# VM3300_V0_1.net
KiCad netlist of a schematic drawn in Altium Designer
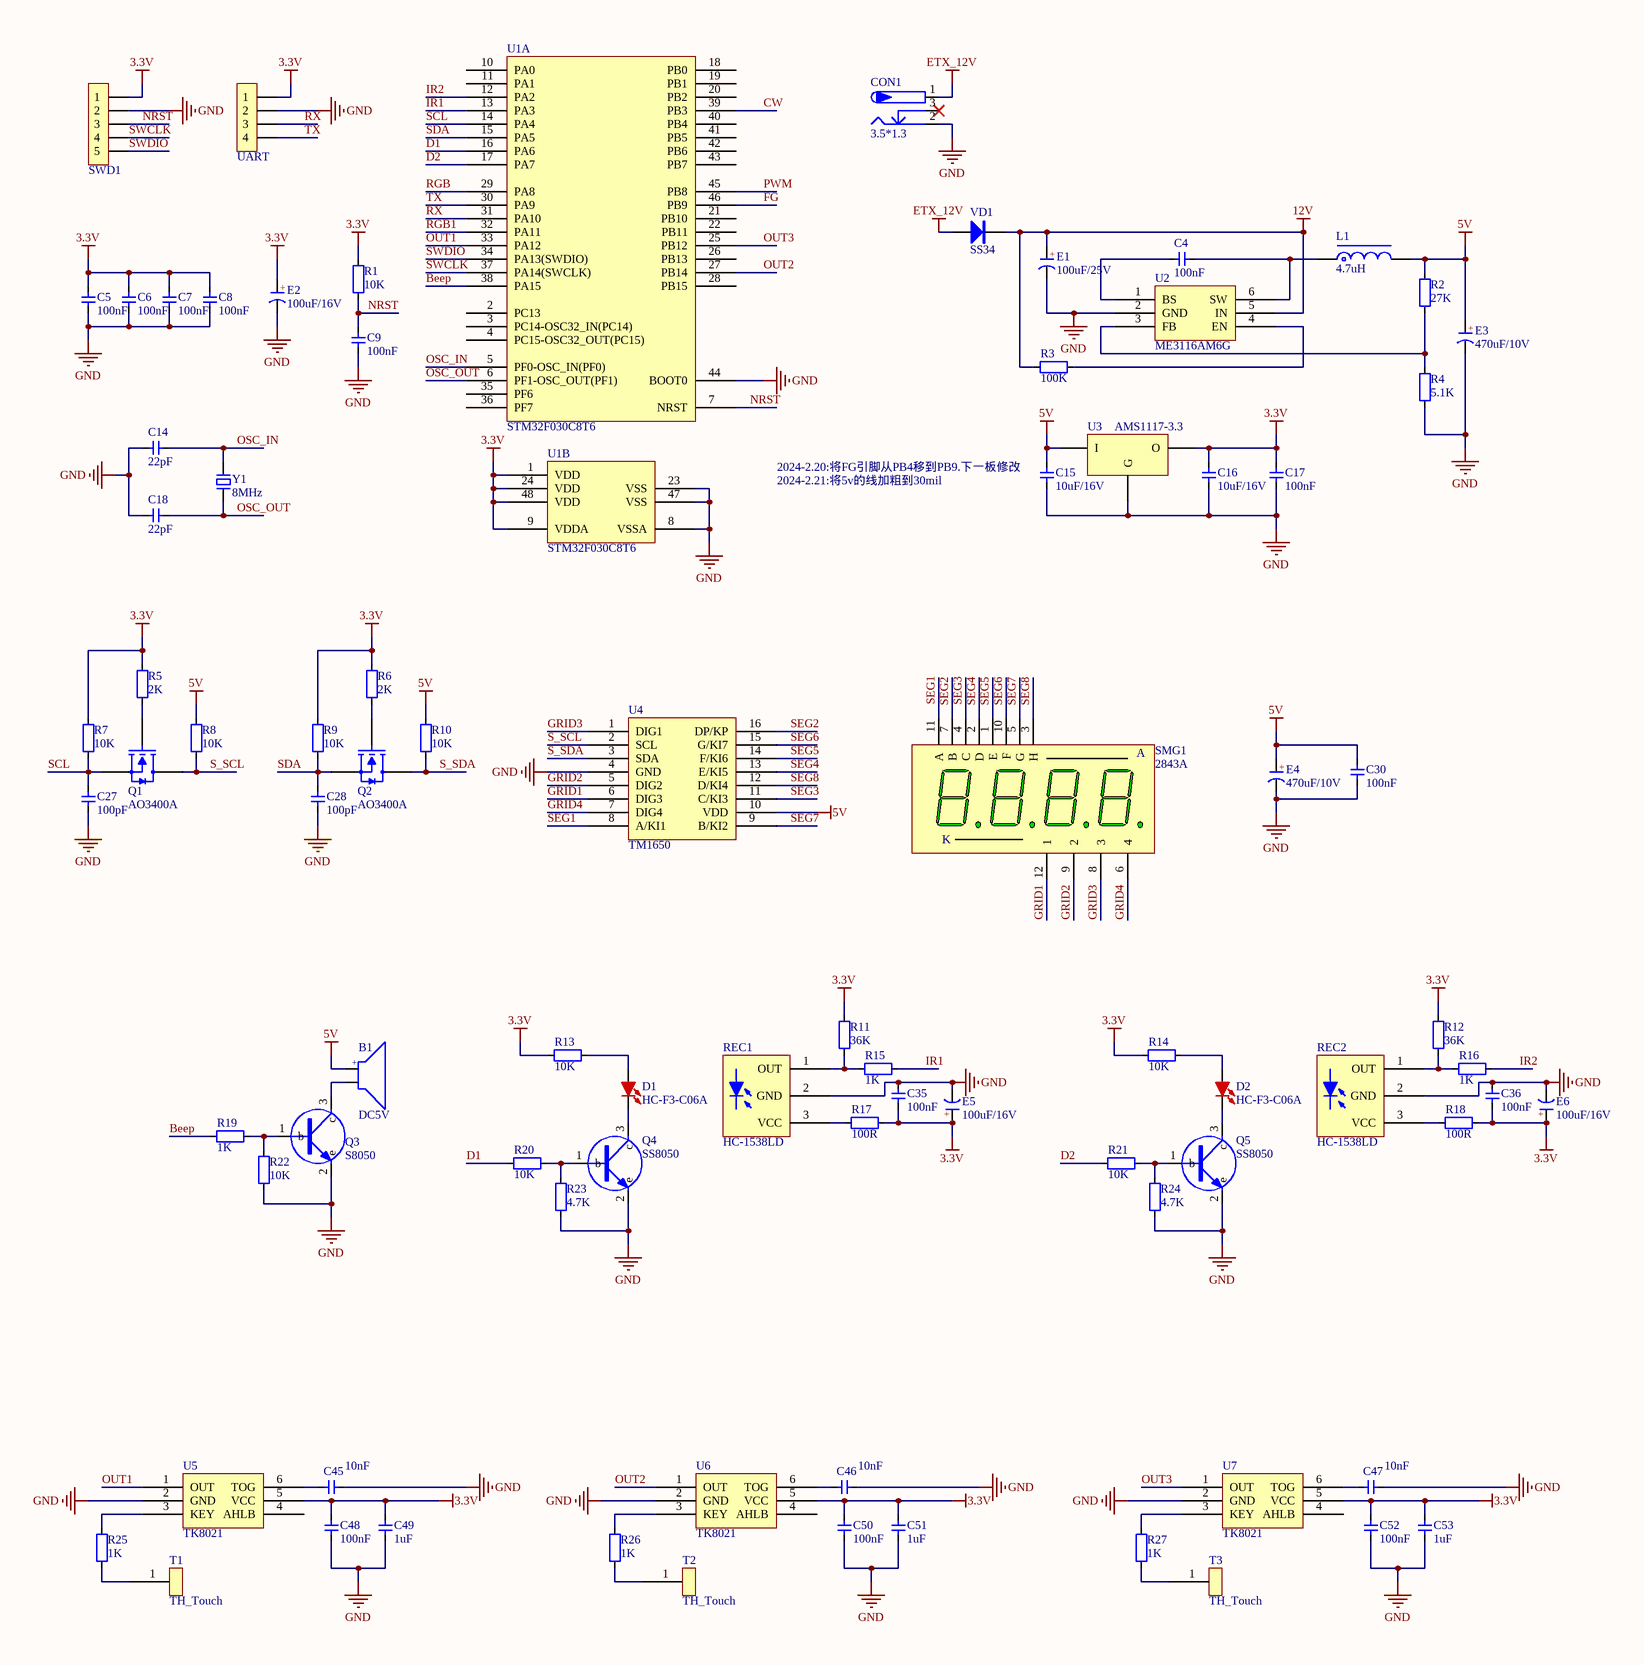
[diagram p0: VM3300_V0.1.SchDoc, left]
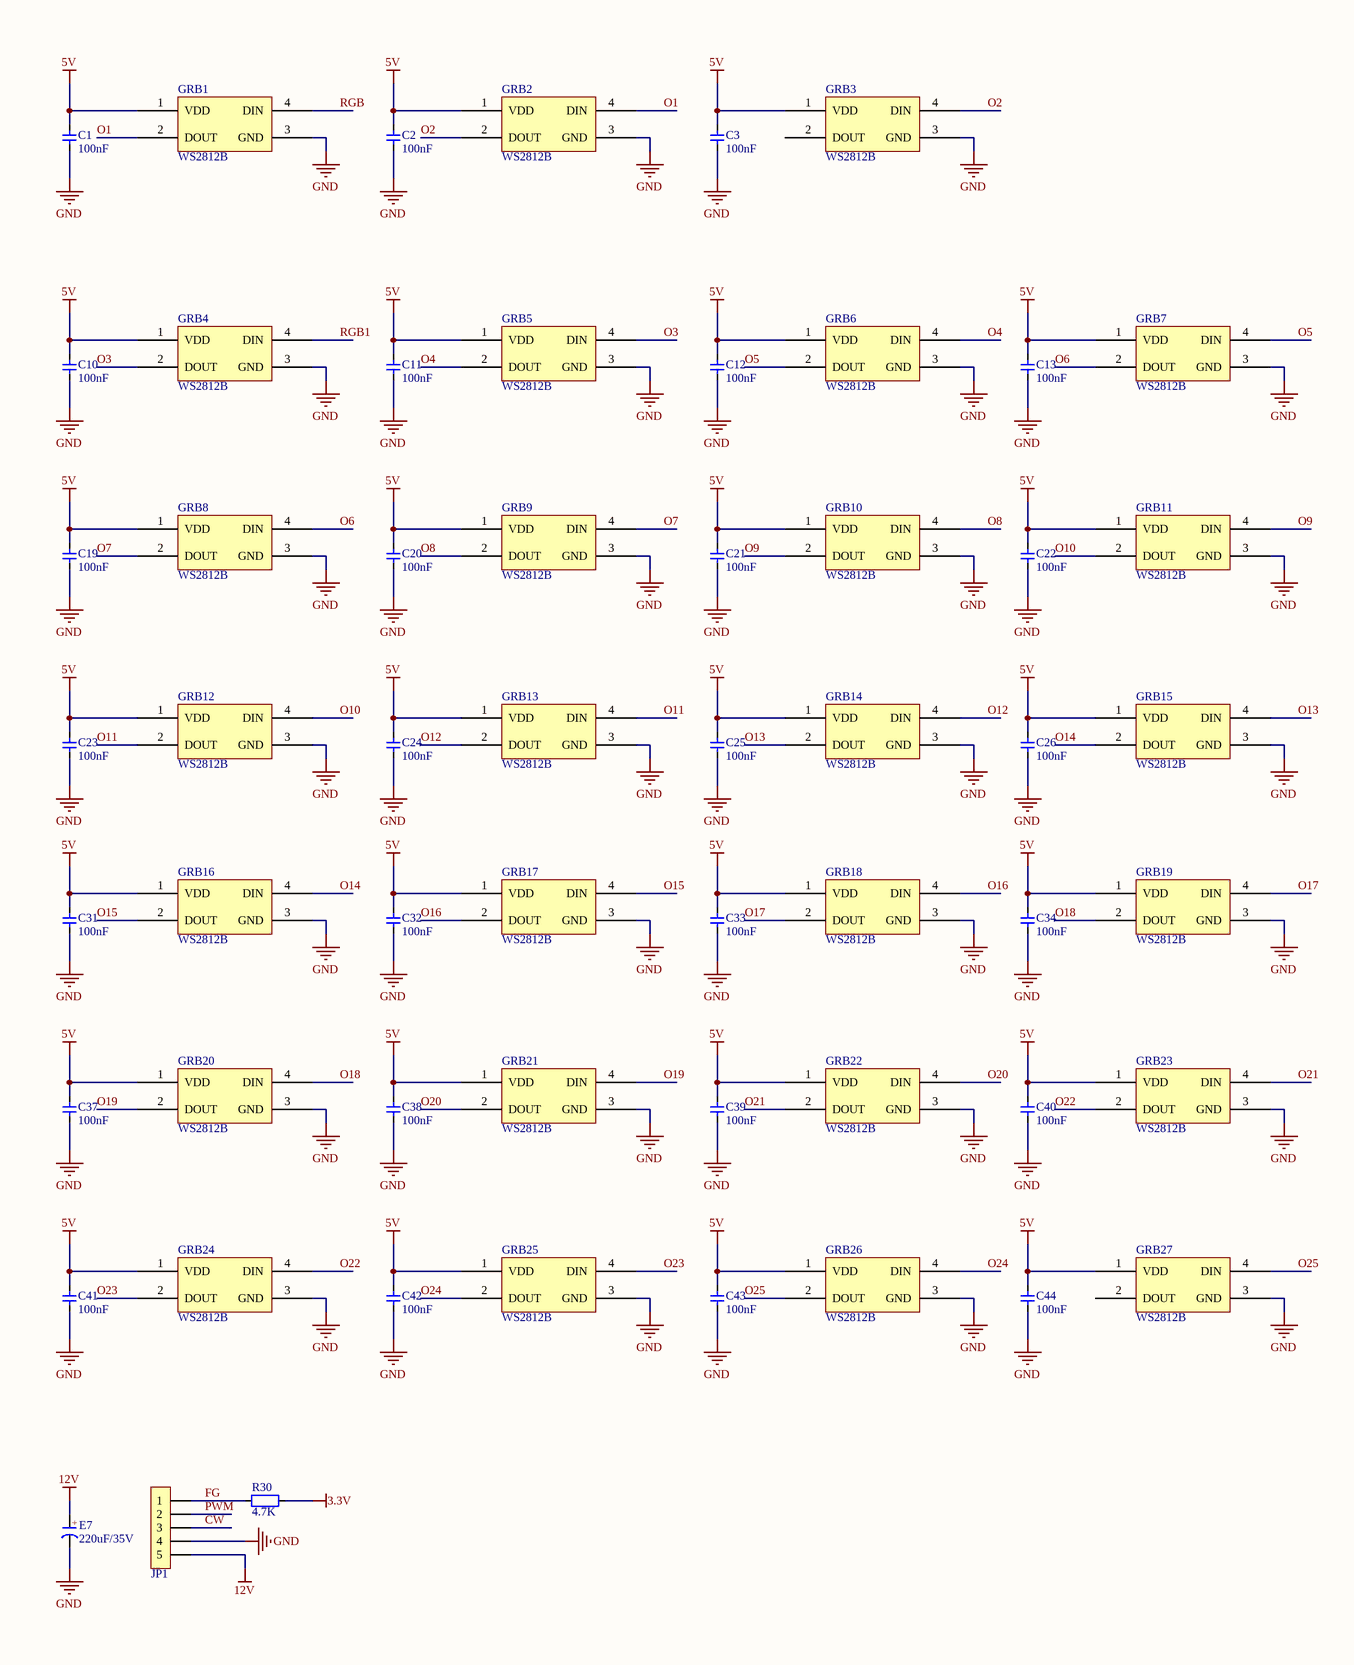
[diagram p1: VM3300_V0.1.SchDoc, right]

(export (version "E")
  (design (tool "Eeschema 10.0.6"))
  (components
    (comp (ref "B1")
      (value "DC5V")
      (footprint "BEEP 7.6x12x7.5")
      (description "蜂鸣器")
      (fields (field (name "版权归属") "源创客"))
      (libsource (lib "模块器件") (part "BEEP"))
    )
    (comp (ref "C1")
      (value "100nF")
      (footprint "C 0603")
      (description "无极性贴片电容")
      (fields (field (name "版权归属") "源创客"))
      (libsource (lib "电容") (part "C"))
    )
    (comp (ref "C2")
      (value "100nF")
      (footprint "C 0603")
      (description "无极性贴片电容")
      (fields (field (name "版权归属") "源创客"))
      (libsource (lib "电容") (part "C"))
    )
    (comp (ref "C3")
      (value "100nF")
      (footprint "C 0603")
      (description "无极性贴片电容")
      (fields (field (name "版权归属") "源创客"))
      (libsource (lib "电容") (part "C"))
    )
    (comp (ref "C4")
      (value "100nF")
      (footprint "C 0603")
      (description "无极性贴片电容")
      (fields (field (name "版权归属") "源创客"))
      (libsource (lib "电容") (part "C"))
    )
    (comp (ref "C5")
      (value "100nF")
      (footprint "C 0603")
      (description "无极性贴片电容")
      (fields (field (name "版权归属") "源创客"))
      (libsource (lib "电容") (part "C"))
    )
    (comp (ref "C6")
      (value "100nF")
      (footprint "C 0603")
      (description "无极性贴片电容")
      (fields (field (name "版权归属") "源创客"))
      (libsource (lib "电容") (part "C"))
    )
    (comp (ref "C7")
      (value "100nF")
      (footprint "C 0603")
      (description "无极性贴片电容")
      (fields (field (name "版权归属") "源创客"))
      (libsource (lib "电容") (part "C"))
    )
    (comp (ref "C8")
      (value "100nF")
      (footprint "C 0603")
      (description "无极性贴片电容")
      (fields (field (name "版权归属") "源创客"))
      (libsource (lib "电容") (part "C"))
    )
    (comp (ref "C9")
      (value "100nF")
      (footprint "C 0603")
      (description "无极性贴片电容")
      (fields (field (name "版权归属") "源创客"))
      (libsource (lib "电容") (part "C"))
    )
    (comp (ref "C10")
      (value "100nF")
      (footprint "C 0603")
      (description "无极性贴片电容")
      (fields (field (name "版权归属") "源创客"))
      (libsource (lib "电容") (part "C"))
    )
    (comp (ref "C11")
      (value "100nF")
      (footprint "C 0603")
      (description "无极性贴片电容")
      (fields (field (name "版权归属") "源创客"))
      (libsource (lib "电容") (part "C"))
    )
    (comp (ref "C12")
      (value "100nF")
      (footprint "C 0603")
      (description "无极性贴片电容")
      (fields (field (name "版权归属") "源创客"))
      (libsource (lib "电容") (part "C"))
    )
    (comp (ref "C13")
      (value "100nF")
      (footprint "C 0603")
      (description "无极性贴片电容")
      (fields (field (name "版权归属") "源创客"))
      (libsource (lib "电容") (part "C"))
    )
    (comp (ref "C14")
      (value "22pF")
      (footprint "C 0603")
      (description "无极性贴片电容")
      (fields (field (name "版权归属") "源创客"))
      (libsource (lib "电容") (part "C"))
    )
    (comp (ref "C15")
      (value "10uF/16V")
      (footprint "C 0805")
      (description "无极性贴片电容")
      (fields (field (name "版权归属") "源创客"))
      (libsource (lib "电容") (part "C"))
    )
    (comp (ref "C16")
      (value "10uF/16V")
      (footprint "C 0805")
      (description "无极性贴片电容")
      (fields (field (name "版权归属") "源创客"))
      (libsource (lib "电容") (part "C"))
    )
    (comp (ref "C17")
      (value "100nF")
      (footprint "C 0603")
      (description "无极性贴片电容")
      (fields (field (name "版权归属") "源创客"))
      (libsource (lib "电容") (part "C"))
    )
    (comp (ref "C18")
      (value "22pF")
      (footprint "C 0603")
      (description "无极性贴片电容")
      (fields (field (name "版权归属") "源创客"))
      (libsource (lib "电容") (part "C"))
    )
    (comp (ref "C19")
      (value "100nF")
      (footprint "C 0603")
      (description "无极性贴片电容")
      (fields (field (name "版权归属") "源创客"))
      (libsource (lib "电容") (part "C"))
    )
    (comp (ref "C20")
      (value "100nF")
      (footprint "C 0603")
      (description "无极性贴片电容")
      (fields (field (name "版权归属") "源创客"))
      (libsource (lib "电容") (part "C"))
    )
    (comp (ref "C21")
      (value "100nF")
      (footprint "C 0603")
      (description "无极性贴片电容")
      (fields (field (name "版权归属") "源创客"))
      (libsource (lib "电容") (part "C"))
    )
    (comp (ref "C22")
      (value "100nF")
      (footprint "C 0603")
      (description "无极性贴片电容")
      (fields (field (name "版权归属") "源创客"))
      (libsource (lib "电容") (part "C"))
    )
    (comp (ref "C23")
      (value "100nF")
      (footprint "C 0603")
      (description "无极性贴片电容")
      (fields (field (name "版权归属") "源创客"))
      (libsource (lib "电容") (part "C"))
    )
    (comp (ref "C24")
      (value "100nF")
      (footprint "C 0603")
      (description "无极性贴片电容")
      (fields (field (name "版权归属") "源创客"))
      (libsource (lib "电容") (part "C"))
    )
    (comp (ref "C25")
      (value "100nF")
      (footprint "C 0603")
      (description "无极性贴片电容")
      (fields (field (name "版权归属") "源创客"))
      (libsource (lib "电容") (part "C"))
    )
    (comp (ref "C26")
      (value "100nF")
      (footprint "C 0603")
      (description "无极性贴片电容")
      (fields (field (name "版权归属") "源创客"))
      (libsource (lib "电容") (part "C"))
    )
    (comp (ref "C27")
      (value "100pF")
      (footprint "C 0603")
      (description "无极性贴片电容")
      (fields (field (name "版权归属") "源创客"))
      (libsource (lib "电容") (part "C"))
    )
    (comp (ref "C28")
      (value "100pF")
      (footprint "C 0603")
      (description "无极性贴片电容")
      (fields (field (name "版权归属") "源创客"))
      (libsource (lib "电容") (part "C"))
    )
    (comp (ref "C30")
      (value "100nF")
      (footprint "C 0603")
      (description "无极性贴片电容")
      (fields (field (name "版权归属") "源创客"))
      (libsource (lib "电容") (part "C"))
    )
    (comp (ref "C31")
      (value "100nF")
      (footprint "C 0603")
      (description "无极性贴片电容")
      (fields (field (name "版权归属") "源创客"))
      (libsource (lib "电容") (part "C"))
    )
    (comp (ref "C32")
      (value "100nF")
      (footprint "C 0603")
      (description "无极性贴片电容")
      (fields (field (name "版权归属") "源创客"))
      (libsource (lib "电容") (part "C"))
    )
    (comp (ref "C33")
      (value "100nF")
      (footprint "C 0603")
      (description "无极性贴片电容")
      (fields (field (name "版权归属") "源创客"))
      (libsource (lib "电容") (part "C"))
    )
    (comp (ref "C34")
      (value "100nF")
      (footprint "C 0603")
      (description "无极性贴片电容")
      (fields (field (name "版权归属") "源创客"))
      (libsource (lib "电容") (part "C"))
    )
    (comp (ref "C35")
      (value "100nF")
      (footprint "C 0603")
      (description "无极性贴片电容")
      (fields (field (name "版权归属") "源创客"))
      (libsource (lib "电容") (part "C"))
    )
    (comp (ref "C36")
      (value "100nF")
      (footprint "C 0603")
      (description "无极性贴片电容")
      (fields (field (name "版权归属") "源创客"))
      (libsource (lib "电容") (part "C"))
    )
    (comp (ref "C37")
      (value "100nF")
      (footprint "C 0603")
      (description "无极性贴片电容")
      (fields (field (name "版权归属") "源创客"))
      (libsource (lib "电容") (part "C"))
    )
    (comp (ref "C38")
      (value "100nF")
      (footprint "C 0603")
      (description "无极性贴片电容")
      (fields (field (name "版权归属") "源创客"))
      (libsource (lib "电容") (part "C"))
    )
    (comp (ref "C39")
      (value "100nF")
      (footprint "C 0603")
      (description "无极性贴片电容")
      (fields (field (name "版权归属") "源创客"))
      (libsource (lib "电容") (part "C"))
    )
    (comp (ref "C40")
      (value "100nF")
      (footprint "C 0603")
      (description "无极性贴片电容")
      (fields (field (name "版权归属") "源创客"))
      (libsource (lib "电容") (part "C"))
    )
    (comp (ref "C41")
      (value "100nF")
      (footprint "C 0603")
      (description "无极性贴片电容")
      (fields (field (name "版权归属") "源创客"))
      (libsource (lib "电容") (part "C"))
    )
    (comp (ref "C42")
      (value "100nF")
      (footprint "C 0603")
      (description "无极性贴片电容")
      (fields (field (name "版权归属") "源创客"))
      (libsource (lib "电容") (part "C"))
    )
    (comp (ref "C43")
      (value "100nF")
      (footprint "C 0603")
      (description "无极性贴片电容")
      (fields (field (name "版权归属") "源创客"))
      (libsource (lib "电容") (part "C"))
    )
    (comp (ref "C44")
      (value "100nF")
      (footprint "C 0603")
      (description "无极性贴片电容")
      (fields (field (name "版权归属") "源创客"))
      (libsource (lib "电容") (part "C"))
    )
    (comp (ref "C45")
      (value "10nF")
      (footprint "C 0603")
      (description "无极性贴片电容")
      (fields (field (name "版权归属") "源创客"))
      (libsource (lib "电容") (part "C"))
    )
    (comp (ref "C46")
      (value "10nF")
      (footprint "C 0603")
      (description "无极性贴片电容")
      (fields (field (name "版权归属") "源创客"))
      (libsource (lib "电容") (part "C"))
    )
    (comp (ref "C47")
      (value "10nF")
      (footprint "C 0603")
      (description "无极性贴片电容")
      (fields (field (name "版权归属") "源创客"))
      (libsource (lib "电容") (part "C"))
    )
    (comp (ref "C48")
      (value "100nF")
      (footprint "C 0603")
      (description "无极性贴片电容")
      (fields (field (name "版权归属") "源创客"))
      (libsource (lib "电容") (part "C"))
    )
    (comp (ref "C49")
      (value "1uF")
      (footprint "C 0603")
      (description "无极性贴片电容")
      (fields (field (name "版权归属") "源创客"))
      (libsource (lib "电容") (part "C"))
    )
    (comp (ref "C50")
      (value "100nF")
      (footprint "C 0603")
      (description "无极性贴片电容")
      (fields (field (name "版权归属") "源创客"))
      (libsource (lib "电容") (part "C"))
    )
    (comp (ref "C51")
      (value "1uF")
      (footprint "C 0603")
      (description "无极性贴片电容")
      (fields (field (name "版权归属") "源创客"))
      (libsource (lib "电容") (part "C"))
    )
    (comp (ref "C52")
      (value "100nF")
      (footprint "C 0603")
      (description "无极性贴片电容")
      (fields (field (name "版权归属") "源创客"))
      (libsource (lib "电容") (part "C"))
    )
    (comp (ref "C53")
      (value "1uF")
      (footprint "C 0603")
      (description "无极性贴片电容")
      (fields (field (name "版权归属") "源创客"))
      (libsource (lib "电容") (part "C"))
    )
    (comp (ref "CON1")
      (value "3.5*1.3")
      (footprint "DC-005")
      (description "低压电源接口")
      (fields (field (name "版权归属") "源创客"))
      (libsource (lib "接口类") (part "P-DC"))
    )
    (comp (ref "D1")
      (value "HC-F3-C06A")
      (footprint "HC-F3-C06A")
      (description "红外发射管")
      (libsource (lib "传感器") (part "HC-F3-C06A"))
    )
    (comp (ref "D2")
      (value "HC-F3-C06A")
      (footprint "HC-F3-C06A")
      (description "红外发射管")
      (libsource (lib "传感器") (part "HC-F3-C06A"))
    )
    (comp (ref "E1")
      (value "100uF/25V")
      (footprint "CAP 2.0*5*11 - BK")
      (description "直插电解电容")
      (fields (field (name "版权归属") "源创客"))
      (libsource (lib "电容") (part "C-CAP"))
    )
    (comp (ref "E2")
      (value "100uF/16V")
      (footprint "CAP 2.0*5*11 - BK")
      (description "直插电解电容")
      (fields (field (name "版权归属") "源创客"))
      (libsource (lib "电容") (part "C-CAP"))
    )
    (comp (ref "E3")
      (value "470uF/10V")
      (footprint "CAP 2.5*6.3*11.2 - BK")
      (description "直插电解电容")
      (fields (field (name "版权归属") "源创客"))
      (libsource (lib "电容") (part "C-CAP"))
    )
    (comp (ref "E4")
      (value "470uF/10V")
      (footprint "CAP 2.5*6.3*11.2 - BK")
      (description "直插电解电容")
      (fields (field (name "版权归属") "源创客"))
      (libsource (lib "电容") (part "C-CAP"))
    )
    (comp (ref "E5")
      (value "100uF/16V")
      (footprint "CAP 2.0*5*11 - BK")
      (description "直插电解电容")
      (fields (field (name "版权归属") "源创客"))
      (libsource (lib "电容") (part "C-CAP"))
    )
    (comp (ref "E6")
      (value "100uF/16V")
      (footprint "CAP 2.0*5*11 - BK")
      (description "直插电解电容")
      (fields (field (name "版权归属") "源创客"))
      (libsource (lib "电容") (part "C-CAP"))
    )
    (comp (ref "E7")
      (value "220uF/35V")
      (footprint "CAP 3.5*8*11.5 - BK")
      (description "直插电解电容")
      (fields (field (name "版权归属") "源创客"))
      (libsource (lib "电容") (part "C-CAP"))
    )
    (comp (ref "GRB1") (value "WS2812B") (footprint "WS2812B-3528") (libsource (lib "LED") (part "WS2812B")))
    (comp (ref "GRB2") (value "WS2812B") (footprint "WS2812B-3528") (libsource (lib "LED") (part "WS2812B")))
    (comp (ref "GRB3") (value "WS2812B") (footprint "WS2812B-3528") (libsource (lib "LED") (part "WS2812B")))
    (comp (ref "GRB4") (value "WS2812B") (footprint "WS2812B-3528") (libsource (lib "LED") (part "WS2812B")))
    (comp (ref "GRB5") (value "WS2812B") (footprint "WS2812B-3528") (libsource (lib "LED") (part "WS2812B")))
    (comp (ref "GRB6") (value "WS2812B") (footprint "WS2812B-3528") (libsource (lib "LED") (part "WS2812B")))
    (comp (ref "GRB7") (value "WS2812B") (footprint "WS2812B-3528") (libsource (lib "LED") (part "WS2812B")))
    (comp (ref "GRB8") (value "WS2812B") (footprint "WS2812B-3528") (libsource (lib "LED") (part "WS2812B")))
    (comp (ref "GRB9") (value "WS2812B") (footprint "WS2812B-3528") (libsource (lib "LED") (part "WS2812B")))
    (comp (ref "GRB10") (value "WS2812B") (footprint "WS2812B-3528") (libsource (lib "LED") (part "WS2812B")))
    (comp (ref "GRB11") (value "WS2812B") (footprint "WS2812B-3528") (libsource (lib "LED") (part "WS2812B")))
    (comp (ref "GRB12") (value "WS2812B") (footprint "WS2812B-3528") (libsource (lib "LED") (part "WS2812B")))
    (comp (ref "GRB13") (value "WS2812B") (footprint "WS2812B-3528") (libsource (lib "LED") (part "WS2812B")))
    (comp (ref "GRB14") (value "WS2812B") (footprint "WS2812B-3528") (libsource (lib "LED") (part "WS2812B")))
    (comp (ref "GRB15") (value "WS2812B") (footprint "WS2812B-3528") (libsource (lib "LED") (part "WS2812B")))
    (comp (ref "GRB16") (value "WS2812B") (footprint "WS2812B-3528") (libsource (lib "LED") (part "WS2812B")))
    (comp (ref "GRB17") (value "WS2812B") (footprint "WS2812B-3528") (libsource (lib "LED") (part "WS2812B")))
    (comp (ref "GRB18") (value "WS2812B") (footprint "WS2812B-3528") (libsource (lib "LED") (part "WS2812B")))
    (comp (ref "GRB19") (value "WS2812B") (footprint "WS2812B-3528") (libsource (lib "LED") (part "WS2812B")))
    (comp (ref "GRB20") (value "WS2812B") (footprint "WS2812B-3528") (libsource (lib "LED") (part "WS2812B")))
    (comp (ref "GRB21") (value "WS2812B") (footprint "WS2812B-3528") (libsource (lib "LED") (part "WS2812B")))
    (comp (ref "GRB22") (value "WS2812B") (footprint "WS2812B-3528") (libsource (lib "LED") (part "WS2812B")))
    (comp (ref "GRB23") (value "WS2812B") (footprint "WS2812B-3528") (libsource (lib "LED") (part "WS2812B")))
    (comp (ref "GRB24") (value "WS2812B") (footprint "WS2812B-3528") (libsource (lib "LED") (part "WS2812B")))
    (comp (ref "GRB25") (value "WS2812B") (footprint "WS2812B-3528") (libsource (lib "LED") (part "WS2812B")))
    (comp (ref "GRB26") (value "WS2812B") (footprint "WS2812B-3528") (libsource (lib "LED") (part "WS2812B")))
    (comp (ref "GRB27") (value "WS2812B") (footprint "WS2812B-3528") (libsource (lib "LED") (part "WS2812B")))
    (comp (ref "JP1")
      (value "HDR-1X5")
      (footprint "XH2.54-5P")
      (description "5P接插件")
      (fields (field (name "版权归属") "源创客"))
      (libsource (lib "排针-排母") (part "Header 5"))
    )
    (comp (ref "L1")
      (value "4.7uH")
      (footprint "CD32")
      (description "贴片功率电感")
      (fields (field (name "版权归属") "源创客"))
      (libsource (lib "电感") (part "L-CD"))
    )
    (comp (ref "Q1")
      (value "AO3400A")
      (footprint "SOT23-3")
      (description "N-MOS")
      (libsource (lib "三极管") (part "AO3400A"))
    )
    (comp (ref "Q2")
      (value "AO3400A")
      (footprint "SOT23-3")
      (description "N-MOS")
      (libsource (lib "三极管") (part "AO3400A"))
    )
    (comp (ref "Q3") (value "S8050") (footprint "SOT23-3L") (libsource (lib "三极管") (part "NPN")))
    (comp (ref "Q4") (value "SS8050") (footprint "SOT23-3L") (libsource (lib "三极管") (part "NPN")))
    (comp (ref "Q5") (value "SS8050") (footprint "SOT23-3L") (libsource (lib "三极管") (part "NPN")))
    (comp (ref "R1")
      (value "10K")
      (footprint "R 0603")
      (description "贴片电阻")
      (fields (field (name "版权归属") "源创客"))
      (libsource (lib "电阻") (part "R"))
    )
    (comp (ref "R2")
      (value "27K")
      (footprint "R 0603")
      (description "贴片电阻")
      (fields (field (name "版权归属") "源创客"))
      (libsource (lib "电阻") (part "R"))
    )
    (comp (ref "R3")
      (value "100K")
      (footprint "R 0603")
      (description "贴片电阻")
      (fields (field (name "版权归属") "源创客"))
      (libsource (lib "") (part "R_1"))
    )
    (comp (ref "R4")
      (value "5.1K")
      (footprint "R 0603")
      (description "贴片电阻")
      (fields (field (name "版权归属") "源创客"))
      (libsource (lib "电阻") (part "R"))
    )
    (comp (ref "R5")
      (value "2K")
      (footprint "R 0603")
      (description "贴片电阻")
      (fields (field (name "版权归属") "源创客"))
      (libsource (lib "电阻") (part "R"))
    )
    (comp (ref "R6")
      (value "2K")
      (footprint "R 0603")
      (description "贴片电阻")
      (fields (field (name "版权归属") "源创客"))
      (libsource (lib "电阻") (part "R"))
    )
    (comp (ref "R7")
      (value "10K")
      (footprint "R 0603")
      (description "贴片电阻")
      (fields (field (name "版权归属") "源创客"))
      (libsource (lib "电阻") (part "R"))
    )
    (comp (ref "R8")
      (value "10K")
      (footprint "R 0603")
      (description "贴片电阻")
      (fields (field (name "版权归属") "源创客"))
      (libsource (lib "电阻") (part "R"))
    )
    (comp (ref "R9")
      (value "10K")
      (footprint "R 0603")
      (description "贴片电阻")
      (fields (field (name "版权归属") "源创客"))
      (libsource (lib "电阻") (part "R"))
    )
    (comp (ref "R10")
      (value "10K")
      (footprint "R 0603")
      (description "贴片电阻")
      (fields (field (name "版权归属") "源创客"))
      (libsource (lib "电阻") (part "R"))
    )
    (comp (ref "R11")
      (value "36K")
      (footprint "R 0603")
      (description "贴片电阻")
      (fields (field (name "版权归属") "源创客"))
      (libsource (lib "电阻") (part "R"))
    )
    (comp (ref "R12")
      (value "36K")
      (footprint "R 0603")
      (description "贴片电阻")
      (fields (field (name "版权归属") "源创客"))
      (libsource (lib "电阻") (part "R"))
    )
    (comp (ref "R13")
      (value "10K")
      (footprint "R 0603")
      (description "贴片电阻")
      (fields (field (name "版权归属") "源创客"))
      (libsource (lib "") (part "R_1"))
    )
    (comp (ref "R14")
      (value "10K")
      (footprint "R 0603")
      (description "贴片电阻")
      (fields (field (name "版权归属") "源创客"))
      (libsource (lib "") (part "R_1"))
    )
    (comp (ref "R15")
      (value "1K")
      (footprint "R 0603")
      (description "贴片电阻")
      (fields (field (name "版权归属") "源创客"))
      (libsource (lib "") (part "R_1"))
    )
    (comp (ref "R16")
      (value "1K")
      (footprint "R 0603")
      (description "贴片电阻")
      (fields (field (name "版权归属") "源创客"))
      (libsource (lib "") (part "R_1"))
    )
    (comp (ref "R17")
      (value "100R")
      (footprint "R 0603")
      (description "贴片电阻")
      (fields (field (name "版权归属") "源创客"))
      (libsource (lib "") (part "R_1"))
    )
    (comp (ref "R18")
      (value "100R")
      (footprint "R 0603")
      (description "贴片电阻")
      (fields (field (name "版权归属") "源创客"))
      (libsource (lib "") (part "R_1"))
    )
    (comp (ref "R19")
      (value "1K")
      (footprint "R 0603")
      (description "贴片电阻")
      (fields (field (name "版权归属") "源创客"))
      (libsource (lib "") (part "R_1"))
    )
    (comp (ref "R20")
      (value "10K")
      (footprint "R 0603")
      (description "贴片电阻")
      (fields (field (name "版权归属") "源创客"))
      (libsource (lib "") (part "R_1"))
    )
    (comp (ref "R21")
      (value "10K")
      (footprint "R 0603")
      (description "贴片电阻")
      (fields (field (name "版权归属") "源创客"))
      (libsource (lib "") (part "R_1"))
    )
    (comp (ref "R22")
      (value "10K")
      (footprint "R 0603")
      (description "贴片电阻")
      (fields (field (name "版权归属") "源创客"))
      (libsource (lib "电阻") (part "R"))
    )
    (comp (ref "R23")
      (value "4.7K")
      (footprint "R 0603")
      (description "贴片电阻")
      (fields (field (name "版权归属") "源创客"))
      (libsource (lib "电阻") (part "R"))
    )
    (comp (ref "R24")
      (value "4.7K")
      (footprint "R 0603")
      (description "贴片电阻")
      (fields (field (name "版权归属") "源创客"))
      (libsource (lib "电阻") (part "R"))
    )
    (comp (ref "R25")
      (value "1K")
      (footprint "R 0603")
      (description "贴片电阻")
      (fields (field (name "版权归属") "源创客"))
      (libsource (lib "电阻") (part "R"))
    )
    (comp (ref "R26")
      (value "1K")
      (footprint "R 0603")
      (description "贴片电阻")
      (fields (field (name "版权归属") "源创客"))
      (libsource (lib "电阻") (part "R"))
    )
    (comp (ref "R27")
      (value "1K")
      (footprint "R 0603")
      (description "贴片电阻")
      (fields (field (name "版权归属") "源创客"))
      (libsource (lib "电阻") (part "R"))
    )
    (comp (ref "R30")
      (value "4.7K")
      (footprint "R 0603")
      (description "贴片电阻")
      (fields (field (name "版权归属") "源创客"))
      (libsource (lib "") (part "R_1"))
    )
    (comp (ref "REC1")
      (value "HC-1538LD")
      (footprint "HC-1538LD-W")
      (description "红外接收管")
      (libsource (lib "传感器") (part "HC-1538LD"))
    )
    (comp (ref "REC2")
      (value "HC-1538LD")
      (footprint "HC-1538LD-W")
      (description "红外接收管")
      (libsource (lib "传感器") (part "HC-1538LD"))
    )
    (comp (ref "SMG1")
      (value "2843A")
      (footprint "SMG 0.28_4P_JOANLAB")
      (description "JOANLAB-0.28寸4位共阴数码管")
      (fields (field (name "版权归属") "源创客"))
      (libsource (lib "显示器件") (part "2843A"))
    )
    (comp (ref "SWD1")
      (value "HDR-1X5")
      (footprint "SWD_JOANLAB")
      (description "5P接插件")
      (fields (field (name "版权归属") "源创客"))
      (libsource (lib "排针-排母") (part "Header 5"))
    )
    (comp (ref "T1")
      (value "TH_Touch")
      (footprint "TH_Touch")
      (description "触摸弹簧，用于触摸感应")
      (libsource (lib "模块器件") (part "TH_Touch"))
    )
    (comp (ref "T2")
      (value "TH_Touch")
      (footprint "TH_Touch")
      (description "触摸弹簧，用于触摸感应")
      (libsource (lib "模块器件") (part "TH_Touch"))
    )
    (comp (ref "T3")
      (value "TH_Touch")
      (footprint "TH_Touch")
      (description "触摸弹簧，用于触摸感应")
      (libsource (lib "模块器件") (part "TH_Touch"))
    )
    (comp (ref "U1")
      (value "STM32F030C8T6")
      (footprint "STM32F030C8T6")
      (libsource (lib "STM32系列单片机") (part "STM32F030C8T6"))
    )
    (comp (ref "U2")
      (value "ME3116AM6G")
      (footprint "ME3116AM6G")
      (description "DC-DC电源芯片  24-40V->5V")
      (libsource (lib "变压器") (part "ME3116AM6G"))
    )
    (comp (ref "U3")
      (value "AMS1117-3.3")
      (footprint "AMS1117-3.3")
      (description "转3.3V电压")
      (libsource (lib "变压器") (part "AMS1117-3.3"))
    )
    (comp (ref "U4")
      (value "TM1650")
      (footprint "TM1650")
      (description "TM1650是一种带键盘扫描接口的LED（发光二极管显示器）驱动控制专用IC,内部集成有MCU\r\n数字接口、数据锁存器、LED驱动、键盘扫描等电路。")
      (libsource (lib "显示芯片") (part "TM1650"))
    )
    (comp (ref "U5")
      (value "TK8021")
      (footprint "TK8021")
      (description "单通道自校正触摸感应芯片")
      (libsource (lib "常用芯片") (part "TTP2233"))
    )
    (comp (ref "U6")
      (value "TK8021")
      (footprint "TK8021")
      (description "单通道自校正触摸感应芯片")
      (libsource (lib "常用芯片") (part "TTP2233"))
    )
    (comp (ref "U7")
      (value "TK8021")
      (footprint "TK8021")
      (description "单通道自校正触摸感应芯片")
      (libsource (lib "常用芯片") (part "TTP2233"))
    )
    (comp (ref "UART")
      (value "HDR-1X4")
      (footprint "XH2.54-4P")
      (description "4P接插件")
      (fields (field (name "版权归属") "源创客"))
      (libsource (lib "排针-排母") (part "Header 4"))
    )
    (comp (ref "VD1")
      (value "SS34")
      (footprint "SMA")
      (description "肖特基二极管")
      (fields (field (name "版权归属") "源创客"))
      (libsource (lib "二极管-整流桥") (part "SS34"))
    )
    (comp (ref "Y1")
      (value "8MHz")
      (footprint "XTAL-49S SMD")
      (description "2脚晶振")
      (fields (field (name "版权归属") "源创客"))
      (libsource (lib "晶振") (part "XTAL-2"))
    )
  )
  (nets
    (net (code "1") (name "/Beep") (class "Default")
      (node (ref "R19") (pin "1") (pinfunction "1_1") (pintype "passive"))
      (node (ref "U1") (pin "38") (pinfunction "PA15_38") (pintype "passive"))
    )
    (net (code "2") (name "/CW") (class "Default")
      (node (ref "JP1") (pin "3") (pinfunction "3_3") (pintype "passive"))
      (node (ref "U1") (pin "39") (pinfunction "PB3_39") (pintype "passive"))
    )
    (net (code "3") (name "/D1") (class "Default")
      (node (ref "R20") (pin "1") (pinfunction "1_1") (pintype "passive"))
      (node (ref "U1") (pin "16") (pinfunction "PA6_16") (pintype "passive"))
    )
    (net (code "4") (name "/D2") (class "Default")
      (node (ref "R21") (pin "1") (pinfunction "1_1") (pintype "passive"))
      (node (ref "U1") (pin "17") (pinfunction "PA7_17") (pintype "passive"))
    )
    (net (code "5") (name "/FG") (class "Default")
      (node (ref "JP1") (pin "1") (pinfunction "1_1") (pintype "passive"))
      (node (ref "R30") (pin "1") (pinfunction "1_1") (pintype "passive"))
      (node (ref "U1") (pin "46") (pinfunction "PB9_46") (pintype "passive"))
    )
    (net (code "6") (name "/GRID1") (class "Default")
      (node (ref "SMG1") (pin "12") (pinfunction "1_12") (pintype "passive"))
      (node (ref "U4") (pin "6") (pinfunction "DIG3_6") (pintype "passive"))
    )
    (net (code "7") (name "/GRID2") (class "Default")
      (node (ref "SMG1") (pin "9") (pinfunction "2_9") (pintype "passive"))
      (node (ref "U4") (pin "5") (pinfunction "DIG2_5") (pintype "passive"))
    )
    (net (code "8") (name "/GRID3") (class "Default")
      (node (ref "SMG1") (pin "8") (pinfunction "3_8") (pintype "passive"))
      (node (ref "U4") (pin "1") (pinfunction "DIG1_1") (pintype "passive"))
    )
    (net (code "9") (name "/GRID4") (class "Default")
      (node (ref "SMG1") (pin "6") (pinfunction "4_6") (pintype "passive"))
      (node (ref "U4") (pin "7") (pinfunction "DIG4_7") (pintype "passive"))
    )
    (net (code "10") (name "/IR1") (class "Default")
      (node (ref "R15") (pin "2") (pinfunction "2_2") (pintype "passive"))
      (node (ref "U1") (pin "13") (pinfunction "PA3_13") (pintype "passive"))
    )
    (net (code "11") (name "/IR2") (class "Default")
      (node (ref "R16") (pin "2") (pinfunction "2_2") (pintype "passive"))
      (node (ref "U1") (pin "12") (pinfunction "PA2_12") (pintype "passive"))
    )
    (net (code "12") (name "/NRST") (class "Default")
      (node (ref "C9") (pin "2") (pinfunction "2_2") (pintype "passive"))
      (node (ref "R1") (pin "1") (pinfunction "1_1") (pintype "passive"))
      (node (ref "SWD1") (pin "3") (pinfunction "3_3") (pintype "passive"))
      (node (ref "U1") (pin "7") (pinfunction "NRST_7") (pintype "passive"))
    )
    (net (code "13") (name "/O1") (class "Default")
      (node (ref "GRB1") (pin "2") (pinfunction "DOUT_2") (pintype "passive"))
      (node (ref "GRB2") (pin "4") (pinfunction "DIN_4") (pintype "passive"))
    )
    (net (code "14") (name "/O2") (class "Default")
      (node (ref "GRB2") (pin "2") (pinfunction "DOUT_2") (pintype "passive"))
      (node (ref "GRB3") (pin "4") (pinfunction "DIN_4") (pintype "passive"))
    )
    (net (code "15") (name "/O3") (class "Default")
      (node (ref "GRB4") (pin "2") (pinfunction "DOUT_2") (pintype "passive"))
      (node (ref "GRB5") (pin "4") (pinfunction "DIN_4") (pintype "passive"))
    )
    (net (code "16") (name "/O4") (class "Default")
      (node (ref "GRB5") (pin "2") (pinfunction "DOUT_2") (pintype "passive"))
      (node (ref "GRB6") (pin "4") (pinfunction "DIN_4") (pintype "passive"))
    )
    (net (code "17") (name "/O5") (class "Default")
      (node (ref "GRB6") (pin "2") (pinfunction "DOUT_2") (pintype "passive"))
      (node (ref "GRB7") (pin "4") (pinfunction "DIN_4") (pintype "passive"))
    )
    (net (code "18") (name "/O6") (class "Default")
      (node (ref "GRB7") (pin "2") (pinfunction "DOUT_2") (pintype "passive"))
      (node (ref "GRB8") (pin "4") (pinfunction "DIN_4") (pintype "passive"))
    )
    (net (code "19") (name "/O7") (class "Default")
      (node (ref "GRB8") (pin "2") (pinfunction "DOUT_2") (pintype "passive"))
      (node (ref "GRB9") (pin "4") (pinfunction "DIN_4") (pintype "passive"))
    )
    (net (code "20") (name "/O8") (class "Default")
      (node (ref "GRB10") (pin "4") (pinfunction "DIN_4") (pintype "passive"))
      (node (ref "GRB9") (pin "2") (pinfunction "DOUT_2") (pintype "passive"))
    )
    (net (code "21") (name "/O9") (class "Default")
      (node (ref "GRB10") (pin "2") (pinfunction "DOUT_2") (pintype "passive"))
      (node (ref "GRB11") (pin "4") (pinfunction "DIN_4") (pintype "passive"))
    )
    (net (code "22") (name "/O10") (class "Default")
      (node (ref "GRB11") (pin "2") (pinfunction "DOUT_2") (pintype "passive"))
      (node (ref "GRB12") (pin "4") (pinfunction "DIN_4") (pintype "passive"))
    )
    (net (code "23") (name "/O11") (class "Default")
      (node (ref "GRB12") (pin "2") (pinfunction "DOUT_2") (pintype "passive"))
      (node (ref "GRB13") (pin "4") (pinfunction "DIN_4") (pintype "passive"))
    )
    (net (code "24") (name "/O12") (class "Default")
      (node (ref "GRB13") (pin "2") (pinfunction "DOUT_2") (pintype "passive"))
      (node (ref "GRB14") (pin "4") (pinfunction "DIN_4") (pintype "passive"))
    )
    (net (code "25") (name "/O13") (class "Default")
      (node (ref "GRB14") (pin "2") (pinfunction "DOUT_2") (pintype "passive"))
      (node (ref "GRB15") (pin "4") (pinfunction "DIN_4") (pintype "passive"))
    )
    (net (code "26") (name "/O14") (class "Default")
      (node (ref "GRB15") (pin "2") (pinfunction "DOUT_2") (pintype "passive"))
      (node (ref "GRB16") (pin "4") (pinfunction "DIN_4") (pintype "passive"))
    )
    (net (code "27") (name "/O15") (class "Default")
      (node (ref "GRB16") (pin "2") (pinfunction "DOUT_2") (pintype "passive"))
      (node (ref "GRB17") (pin "4") (pinfunction "DIN_4") (pintype "passive"))
    )
    (net (code "28") (name "/O16") (class "Default")
      (node (ref "GRB17") (pin "2") (pinfunction "DOUT_2") (pintype "passive"))
      (node (ref "GRB18") (pin "4") (pinfunction "DIN_4") (pintype "passive"))
    )
    (net (code "29") (name "/O17") (class "Default")
      (node (ref "GRB18") (pin "2") (pinfunction "DOUT_2") (pintype "passive"))
      (node (ref "GRB19") (pin "4") (pinfunction "DIN_4") (pintype "passive"))
    )
    (net (code "30") (name "/O18") (class "Default")
      (node (ref "GRB19") (pin "2") (pinfunction "DOUT_2") (pintype "passive"))
      (node (ref "GRB20") (pin "4") (pinfunction "DIN_4") (pintype "passive"))
    )
    (net (code "31") (name "/O19") (class "Default")
      (node (ref "GRB20") (pin "2") (pinfunction "DOUT_2") (pintype "passive"))
      (node (ref "GRB21") (pin "4") (pinfunction "DIN_4") (pintype "passive"))
    )
    (net (code "32") (name "/O20") (class "Default")
      (node (ref "GRB21") (pin "2") (pinfunction "DOUT_2") (pintype "passive"))
      (node (ref "GRB22") (pin "4") (pinfunction "DIN_4") (pintype "passive"))
    )
    (net (code "33") (name "/O21") (class "Default")
      (node (ref "GRB22") (pin "2") (pinfunction "DOUT_2") (pintype "passive"))
      (node (ref "GRB23") (pin "4") (pinfunction "DIN_4") (pintype "passive"))
    )
    (net (code "34") (name "/O22") (class "Default")
      (node (ref "GRB23") (pin "2") (pinfunction "DOUT_2") (pintype "passive"))
      (node (ref "GRB24") (pin "4") (pinfunction "DIN_4") (pintype "passive"))
    )
    (net (code "35") (name "/O23") (class "Default")
      (node (ref "GRB24") (pin "2") (pinfunction "DOUT_2") (pintype "passive"))
      (node (ref "GRB25") (pin "4") (pinfunction "DIN_4") (pintype "passive"))
    )
    (net (code "36") (name "/O24") (class "Default")
      (node (ref "GRB25") (pin "2") (pinfunction "DOUT_2") (pintype "passive"))
      (node (ref "GRB26") (pin "4") (pinfunction "DIN_4") (pintype "passive"))
    )
    (net (code "37") (name "/O25") (class "Default")
      (node (ref "GRB26") (pin "2") (pinfunction "DOUT_2") (pintype "passive"))
      (node (ref "GRB27") (pin "4") (pinfunction "DIN_4") (pintype "passive"))
    )
    (net (code "38") (name "/OSC_IN") (class "Default")
      (node (ref "C14") (pin "2") (pinfunction "2_2") (pintype "passive"))
      (node (ref "U1") (pin "5") (pinfunction "PF0-OSC_IN(PF0)_5") (pintype "passive"))
      (node (ref "Y1") (pin "2") (pinfunction "2_2") (pintype "passive"))
    )
    (net (code "39") (name "/OSC_OUT") (class "Default")
      (node (ref "C18") (pin "2") (pinfunction "2_2") (pintype "passive"))
      (node (ref "U1") (pin "6") (pinfunction "PF1-OSC_OUT(PF1)_6") (pintype "passive"))
      (node (ref "Y1") (pin "1") (pinfunction "1_1") (pintype "passive"))
    )
    (net (code "40") (name "/OUT1") (class "Default")
      (node (ref "U1") (pin "33") (pinfunction "PA12_33") (pintype "passive"))
      (node (ref "U5") (pin "1") (pinfunction "OUT_1") (pintype "passive"))
    )
    (net (code "41") (name "/OUT2") (class "Default")
      (node (ref "U1") (pin "27") (pinfunction "PB14_27") (pintype "passive"))
      (node (ref "U6") (pin "1") (pinfunction "OUT_1") (pintype "passive"))
    )
    (net (code "42") (name "/OUT3") (class "Default")
      (node (ref "U1") (pin "25") (pinfunction "PB12_25") (pintype "passive"))
      (node (ref "U7") (pin "1") (pinfunction "OUT_1") (pintype "passive"))
    )
    (net (code "43") (name "/PWM") (class "Default")
      (node (ref "JP1") (pin "2") (pinfunction "2_2") (pintype "passive"))
      (node (ref "U1") (pin "45") (pinfunction "PB8_45") (pintype "passive"))
    )
    (net (code "44") (name "/RGB") (class "Default")
      (node (ref "GRB1") (pin "4") (pinfunction "DIN_4") (pintype "passive"))
      (node (ref "U1") (pin "29") (pinfunction "PA8_29") (pintype "passive"))
    )
    (net (code "45") (name "/RGB1") (class "Default")
      (node (ref "GRB4") (pin "4") (pinfunction "DIN_4") (pintype "passive"))
      (node (ref "U1") (pin "32") (pinfunction "PA11_32") (pintype "passive"))
    )
    (net (code "46") (name "/RX") (class "Default")
      (node (ref "U1") (pin "31") (pinfunction "PA10_31") (pintype "passive"))
      (node (ref "UART") (pin "3") (pinfunction "3_3") (pintype "passive"))
    )
    (net (code "47") (name "/SCL") (class "Default")
      (node (ref "C27") (pin "2") (pinfunction "2_2") (pintype "passive"))
      (node (ref "Q1") (pin "3") (pinfunction "S_3") (pintype "passive"))
      (node (ref "R7") (pin "1") (pinfunction "1_1") (pintype "passive"))
      (node (ref "U1") (pin "14") (pinfunction "PA4_14") (pintype "passive"))
    )
    (net (code "48") (name "/SDA") (class "Default")
      (node (ref "C28") (pin "2") (pinfunction "2_2") (pintype "passive"))
      (node (ref "Q2") (pin "3") (pinfunction "S_3") (pintype "passive"))
      (node (ref "R9") (pin "1") (pinfunction "1_1") (pintype "passive"))
      (node (ref "U1") (pin "15") (pinfunction "PA5_15") (pintype "passive"))
    )
    (net (code "49") (name "/SEG1") (class "Default")
      (node (ref "SMG1") (pin "11") (pinfunction "A_11") (pintype "passive"))
      (node (ref "U4") (pin "8") (pinfunction "A/KI1_8") (pintype "passive"))
    )
    (net (code "50") (name "/SEG2") (class "Default")
      (node (ref "SMG1") (pin "7") (pinfunction "B_7") (pintype "passive"))
      (node (ref "U4") (pin "16") (pinfunction "DP/KP_16") (pintype "passive"))
    )
    (net (code "51") (name "/SEG3") (class "Default")
      (node (ref "SMG1") (pin "4") (pinfunction "C_4") (pintype "passive"))
      (node (ref "U4") (pin "11") (pinfunction "C/KI3_11") (pintype "passive"))
    )
    (net (code "52") (name "/SEG4") (class "Default")
      (node (ref "SMG1") (pin "2") (pinfunction "D_2") (pintype "passive"))
      (node (ref "U4") (pin "13") (pinfunction "E/KI5_13") (pintype "passive"))
    )
    (net (code "53") (name "/SEG5") (class "Default")
      (node (ref "SMG1") (pin "1") (pinfunction "E_1") (pintype "passive"))
      (node (ref "U4") (pin "14") (pinfunction "F/KI6_14") (pintype "passive"))
    )
    (net (code "54") (name "/SEG6") (class "Default")
      (node (ref "SMG1") (pin "10") (pinfunction "F_10") (pintype "passive"))
      (node (ref "U4") (pin "15") (pinfunction "G/KI7_15") (pintype "passive"))
    )
    (net (code "55") (name "/SEG7") (class "Default")
      (node (ref "SMG1") (pin "5") (pinfunction "G_5") (pintype "passive"))
      (node (ref "U4") (pin "9") (pinfunction "B/KI2_9") (pintype "passive"))
    )
    (net (code "56") (name "/SEG8") (class "Default")
      (node (ref "SMG1") (pin "3") (pinfunction "H_3") (pintype "passive"))
      (node (ref "U4") (pin "12") (pinfunction "D/KI4_12") (pintype "passive"))
    )
    (net (code "57") (name "/SWCLK") (class "Default")
      (node (ref "SWD1") (pin "4") (pinfunction "4_4") (pintype "passive"))
      (node (ref "U1") (pin "37") (pinfunction "PA14(SWCLK)_37") (pintype "passive"))
    )
    (net (code "58") (name "/SWDIO") (class "Default")
      (node (ref "SWD1") (pin "5") (pinfunction "5_5") (pintype "passive"))
      (node (ref "U1") (pin "34") (pinfunction "PA13(SWDIO)_34") (pintype "passive"))
    )
    (net (code "59") (name "/S_SCL") (class "Default")
      (node (ref "Q1") (pin "2") (pinfunction "D_2") (pintype "passive"))
      (node (ref "R8") (pin "1") (pinfunction "1_1") (pintype "passive"))
      (node (ref "U4") (pin "2") (pinfunction "SCL_2") (pintype "passive"))
    )
    (net (code "60") (name "/S_SDA") (class "Default")
      (node (ref "Q2") (pin "2") (pinfunction "D_2") (pintype "passive"))
      (node (ref "R10") (pin "1") (pinfunction "1_1") (pintype "passive"))
      (node (ref "U4") (pin "3") (pinfunction "SDA_3") (pintype "passive"))
    )
    (net (code "61") (name "/TX") (class "Default")
      (node (ref "U1") (pin "30") (pinfunction "PA9_30") (pintype "passive"))
      (node (ref "UART") (pin "4") (pinfunction "4_4") (pintype "passive"))
    )
    (net (code "62") (name "3.3V") (class "Default")
      (node (ref "C16") (pin "2") (pinfunction "2_2") (pintype "passive"))
      (node (ref "C17") (pin "2") (pinfunction "2_2") (pintype "passive"))
      (node (ref "C35") (pin "1") (pinfunction "1_1") (pintype "passive"))
      (node (ref "C36") (pin "1") (pinfunction "1_1") (pintype "passive"))
      (node (ref "C48") (pin "2") (pinfunction "2_2") (pintype "passive"))
      (node (ref "C49") (pin "2") (pinfunction "2_2") (pintype "passive"))
      (node (ref "C5") (pin "2") (pinfunction "2_2") (pintype "passive"))
      (node (ref "C50") (pin "2") (pinfunction "2_2") (pintype "passive"))
      (node (ref "C51") (pin "2") (pinfunction "2_2") (pintype "passive"))
      (node (ref "C52") (pin "2") (pinfunction "2_2") (pintype "passive"))
      (node (ref "C53") (pin "2") (pinfunction "2_2") (pintype "passive"))
      (node (ref "C6") (pin "2") (pinfunction "2_2") (pintype "passive"))
      (node (ref "C7") (pin "2") (pinfunction "2_2") (pintype "passive"))
      (node (ref "C8") (pin "2") (pinfunction "2_2") (pintype "passive"))
      (node (ref "E2") (pin "1") (pinfunction "A_1") (pintype "passive"))
      (node (ref "E5") (pin "1") (pinfunction "A_1") (pintype "passive"))
      (node (ref "E6") (pin "1") (pinfunction "A_1") (pintype "passive"))
      (node (ref "R1") (pin "2") (pinfunction "2_2") (pintype "passive"))
      (node (ref "R11") (pin "2") (pinfunction "2_2") (pintype "passive"))
      (node (ref "R12") (pin "2") (pinfunction "2_2") (pintype "passive"))
      (node (ref "R13") (pin "1") (pinfunction "1_1") (pintype "passive"))
      (node (ref "R14") (pin "1") (pinfunction "1_1") (pintype "passive"))
      (node (ref "R17") (pin "2") (pinfunction "2_2") (pintype "passive"))
      (node (ref "R18") (pin "2") (pinfunction "2_2") (pintype "passive"))
      (node (ref "R30") (pin "2") (pinfunction "2_2") (pintype "passive"))
      (node (ref "R5") (pin "2") (pinfunction "2_2") (pintype "passive"))
      (node (ref "R6") (pin "2") (pinfunction "2_2") (pintype "passive"))
      (node (ref "R7") (pin "2") (pinfunction "2_2") (pintype "passive"))
      (node (ref "R9") (pin "2") (pinfunction "2_2") (pintype "passive"))
      (node (ref "SWD1") (pin "1") (pinfunction "1_1") (pintype "passive"))
      (node (ref "U1") (pin "1") (pinfunction "VDD_1") (pintype "passive"))
      (node (ref "U1") (pin "24") (pinfunction "VDD_24") (pintype "passive"))
      (node (ref "U1") (pin "48") (pinfunction "VDD_48") (pintype "passive"))
      (node (ref "U1") (pin "9") (pinfunction "VDDA_9") (pintype "passive"))
      (node (ref "U3") (pin "2") (pinfunction "O_2") (pintype "passive"))
      (node (ref "U5") (pin "5") (pinfunction "VCC_5") (pintype "passive"))
      (node (ref "U6") (pin "5") (pinfunction "VCC_5") (pintype "passive"))
      (node (ref "U7") (pin "5") (pinfunction "VCC_5") (pintype "passive"))
      (node (ref "UART") (pin "1") (pinfunction "1_1") (pintype "passive"))
    )
    (net (code "63") (name "5V") (class "Default")
      (node (ref "B1") (pin "1") (pinfunction "1_1") (pintype "passive"))
      (node (ref "C1") (pin "2") (pinfunction "2_2") (pintype "passive"))
      (node (ref "C10") (pin "2") (pinfunction "2_2") (pintype "passive"))
      (node (ref "C11") (pin "2") (pinfunction "2_2") (pintype "passive"))
      (node (ref "C12") (pin "2") (pinfunction "2_2") (pintype "passive"))
      (node (ref "C13") (pin "2") (pinfunction "2_2") (pintype "passive"))
      (node (ref "C15") (pin "2") (pinfunction "2_2") (pintype "passive"))
      (node (ref "C19") (pin "2") (pinfunction "2_2") (pintype "passive"))
      (node (ref "C2") (pin "2") (pinfunction "2_2") (pintype "passive"))
      (node (ref "C20") (pin "2") (pinfunction "2_2") (pintype "passive"))
      (node (ref "C21") (pin "2") (pinfunction "2_2") (pintype "passive"))
      (node (ref "C22") (pin "2") (pinfunction "2_2") (pintype "passive"))
      (node (ref "C23") (pin "2") (pinfunction "2_2") (pintype "passive"))
      (node (ref "C24") (pin "2") (pinfunction "2_2") (pintype "passive"))
      (node (ref "C25") (pin "2") (pinfunction "2_2") (pintype "passive"))
      (node (ref "C26") (pin "2") (pinfunction "2_2") (pintype "passive"))
      (node (ref "C3") (pin "2") (pinfunction "2_2") (pintype "passive"))
      (node (ref "C30") (pin "2") (pinfunction "2_2") (pintype "passive"))
      (node (ref "C31") (pin "2") (pinfunction "2_2") (pintype "passive"))
      (node (ref "C32") (pin "2") (pinfunction "2_2") (pintype "passive"))
      (node (ref "C33") (pin "2") (pinfunction "2_2") (pintype "passive"))
      (node (ref "C34") (pin "2") (pinfunction "2_2") (pintype "passive"))
      (node (ref "C37") (pin "2") (pinfunction "2_2") (pintype "passive"))
      (node (ref "C38") (pin "2") (pinfunction "2_2") (pintype "passive"))
      (node (ref "C39") (pin "2") (pinfunction "2_2") (pintype "passive"))
      (node (ref "C40") (pin "2") (pinfunction "2_2") (pintype "passive"))
      (node (ref "C41") (pin "2") (pinfunction "2_2") (pintype "passive"))
      (node (ref "C42") (pin "2") (pinfunction "2_2") (pintype "passive"))
      (node (ref "C43") (pin "2") (pinfunction "2_2") (pintype "passive"))
      (node (ref "C44") (pin "2") (pinfunction "2_2") (pintype "passive"))
      (node (ref "E3") (pin "1") (pinfunction "A_1") (pintype "passive"))
      (node (ref "E4") (pin "1") (pinfunction "A_1") (pintype "passive"))
      (node (ref "GRB1") (pin "1") (pinfunction "VDD_1") (pintype "passive"))
      (node (ref "GRB10") (pin "1") (pinfunction "VDD_1") (pintype "passive"))
      (node (ref "GRB11") (pin "1") (pinfunction "VDD_1") (pintype "passive"))
      (node (ref "GRB12") (pin "1") (pinfunction "VDD_1") (pintype "passive"))
      (node (ref "GRB13") (pin "1") (pinfunction "VDD_1") (pintype "passive"))
      (node (ref "GRB14") (pin "1") (pinfunction "VDD_1") (pintype "passive"))
      (node (ref "GRB15") (pin "1") (pinfunction "VDD_1") (pintype "passive"))
      (node (ref "GRB16") (pin "1") (pinfunction "VDD_1") (pintype "passive"))
      (node (ref "GRB17") (pin "1") (pinfunction "VDD_1") (pintype "passive"))
      (node (ref "GRB18") (pin "1") (pinfunction "VDD_1") (pintype "passive"))
      (node (ref "GRB19") (pin "1") (pinfunction "VDD_1") (pintype "passive"))
      (node (ref "GRB2") (pin "1") (pinfunction "VDD_1") (pintype "passive"))
      (node (ref "GRB20") (pin "1") (pinfunction "VDD_1") (pintype "passive"))
      (node (ref "GRB21") (pin "1") (pinfunction "VDD_1") (pintype "passive"))
      (node (ref "GRB22") (pin "1") (pinfunction "VDD_1") (pintype "passive"))
      (node (ref "GRB23") (pin "1") (pinfunction "VDD_1") (pintype "passive"))
      (node (ref "GRB24") (pin "1") (pinfunction "VDD_1") (pintype "passive"))
      (node (ref "GRB25") (pin "1") (pinfunction "VDD_1") (pintype "passive"))
      (node (ref "GRB26") (pin "1") (pinfunction "VDD_1") (pintype "passive"))
      (node (ref "GRB27") (pin "1") (pinfunction "VDD_1") (pintype "passive"))
      (node (ref "GRB3") (pin "1") (pinfunction "VDD_1") (pintype "passive"))
      (node (ref "GRB4") (pin "1") (pinfunction "VDD_1") (pintype "passive"))
      (node (ref "GRB5") (pin "1") (pinfunction "VDD_1") (pintype "passive"))
      (node (ref "GRB6") (pin "1") (pinfunction "VDD_1") (pintype "passive"))
      (node (ref "GRB7") (pin "1") (pinfunction "VDD_1") (pintype "passive"))
      (node (ref "GRB8") (pin "1") (pinfunction "VDD_1") (pintype "passive"))
      (node (ref "GRB9") (pin "1") (pinfunction "VDD_1") (pintype "passive"))
      (node (ref "L1") (pin "2") (pinfunction "2_2") (pintype "passive"))
      (node (ref "R10") (pin "2") (pinfunction "2_2") (pintype "passive"))
      (node (ref "R2") (pin "2") (pinfunction "2_2") (pintype "passive"))
      (node (ref "R8") (pin "2") (pinfunction "2_2") (pintype "passive"))
      (node (ref "U3") (pin "3") (pinfunction "I_3") (pintype "passive"))
      (node (ref "U4") (pin "10") (pinfunction "VDD_10") (pintype "passive"))
    )
    (net (code "64") (name "12V") (class "Default")
      (node (ref "E1") (pin "1") (pinfunction "A_1") (pintype "passive"))
      (node (ref "E7") (pin "1") (pinfunction "A_1") (pintype "passive"))
      (node (ref "JP1") (pin "5") (pinfunction "5_5") (pintype "passive"))
      (node (ref "R3") (pin "1") (pinfunction "1_1") (pintype "passive"))
      (node (ref "U2") (pin "5") (pinfunction "IN_5") (pintype "passive"))
      (node (ref "VD1") (pin "2") (pinfunction "K_2") (pintype "passive"))
    )
    (net (code "65") (name "ETX_12V") (class "Default")
      (node (ref "CON1") (pin "1") (pintype "power_in"))
      (node (ref "VD1") (pin "1") (pinfunction "A_1") (pintype "passive"))
    )
    (net (code "66") (name "GND") (class "Default")
      (node (ref "C1") (pin "1") (pinfunction "1_1") (pintype "passive"))
      (node (ref "C10") (pin "1") (pinfunction "1_1") (pintype "passive"))
      (node (ref "C11") (pin "1") (pinfunction "1_1") (pintype "passive"))
      (node (ref "C12") (pin "1") (pinfunction "1_1") (pintype "passive"))
      (node (ref "C13") (pin "1") (pinfunction "1_1") (pintype "passive"))
      (node (ref "C14") (pin "1") (pinfunction "1_1") (pintype "passive"))
      (node (ref "C15") (pin "1") (pinfunction "1_1") (pintype "passive"))
      (node (ref "C16") (pin "1") (pinfunction "1_1") (pintype "passive"))
      (node (ref "C17") (pin "1") (pinfunction "1_1") (pintype "passive"))
      (node (ref "C18") (pin "1") (pinfunction "1_1") (pintype "passive"))
      (node (ref "C19") (pin "1") (pinfunction "1_1") (pintype "passive"))
      (node (ref "C2") (pin "1") (pinfunction "1_1") (pintype "passive"))
      (node (ref "C20") (pin "1") (pinfunction "1_1") (pintype "passive"))
      (node (ref "C21") (pin "1") (pinfunction "1_1") (pintype "passive"))
      (node (ref "C22") (pin "1") (pinfunction "1_1") (pintype "passive"))
      (node (ref "C23") (pin "1") (pinfunction "1_1") (pintype "passive"))
      (node (ref "C24") (pin "1") (pinfunction "1_1") (pintype "passive"))
      (node (ref "C25") (pin "1") (pinfunction "1_1") (pintype "passive"))
      (node (ref "C26") (pin "1") (pinfunction "1_1") (pintype "passive"))
      (node (ref "C27") (pin "1") (pinfunction "1_1") (pintype "passive"))
      (node (ref "C28") (pin "1") (pinfunction "1_1") (pintype "passive"))
      (node (ref "C3") (pin "1") (pinfunction "1_1") (pintype "passive"))
      (node (ref "C30") (pin "1") (pinfunction "1_1") (pintype "passive"))
      (node (ref "C31") (pin "1") (pinfunction "1_1") (pintype "passive"))
      (node (ref "C32") (pin "1") (pinfunction "1_1") (pintype "passive"))
      (node (ref "C33") (pin "1") (pinfunction "1_1") (pintype "passive"))
      (node (ref "C34") (pin "1") (pinfunction "1_1") (pintype "passive"))
      (node (ref "C35") (pin "2") (pinfunction "2_2") (pintype "passive"))
      (node (ref "C36") (pin "2") (pinfunction "2_2") (pintype "passive"))
      (node (ref "C37") (pin "1") (pinfunction "1_1") (pintype "passive"))
      (node (ref "C38") (pin "1") (pinfunction "1_1") (pintype "passive"))
      (node (ref "C39") (pin "1") (pinfunction "1_1") (pintype "passive"))
      (node (ref "C40") (pin "1") (pinfunction "1_1") (pintype "passive"))
      (node (ref "C41") (pin "1") (pinfunction "1_1") (pintype "passive"))
      (node (ref "C42") (pin "1") (pinfunction "1_1") (pintype "passive"))
      (node (ref "C43") (pin "1") (pinfunction "1_1") (pintype "passive"))
      (node (ref "C44") (pin "1") (pinfunction "1_1") (pintype "passive"))
      (node (ref "C45") (pin "2") (pinfunction "2_2") (pintype "passive"))
      (node (ref "C46") (pin "2") (pinfunction "2_2") (pintype "passive"))
      (node (ref "C47") (pin "2") (pinfunction "2_2") (pintype "passive"))
      (node (ref "C48") (pin "1") (pinfunction "1_1") (pintype "passive"))
      (node (ref "C49") (pin "1") (pinfunction "1_1") (pintype "passive"))
      (node (ref "C5") (pin "1") (pinfunction "1_1") (pintype "passive"))
      (node (ref "C50") (pin "1") (pinfunction "1_1") (pintype "passive"))
      (node (ref "C51") (pin "1") (pinfunction "1_1") (pintype "passive"))
      (node (ref "C52") (pin "1") (pinfunction "1_1") (pintype "passive"))
      (node (ref "C53") (pin "1") (pinfunction "1_1") (pintype "passive"))
      (node (ref "C6") (pin "1") (pinfunction "1_1") (pintype "passive"))
      (node (ref "C7") (pin "1") (pinfunction "1_1") (pintype "passive"))
      (node (ref "C8") (pin "1") (pinfunction "1_1") (pintype "passive"))
      (node (ref "C9") (pin "1") (pinfunction "1_1") (pintype "passive"))
      (node (ref "CON1") (pin "2") (pintype "power_in"))
      (node (ref "E1") (pin "2") (pinfunction "K_2") (pintype "passive"))
      (node (ref "E2") (pin "2") (pinfunction "K_2") (pintype "passive"))
      (node (ref "E3") (pin "2") (pinfunction "K_2") (pintype "passive"))
      (node (ref "E4") (pin "2") (pinfunction "K_2") (pintype "passive"))
      (node (ref "E5") (pin "2") (pinfunction "K_2") (pintype "passive"))
      (node (ref "E6") (pin "2") (pinfunction "K_2") (pintype "passive"))
      (node (ref "E7") (pin "2") (pinfunction "K_2") (pintype "passive"))
      (node (ref "GRB1") (pin "3") (pinfunction "GND_3") (pintype "passive"))
      (node (ref "GRB10") (pin "3") (pinfunction "GND_3") (pintype "passive"))
      (node (ref "GRB11") (pin "3") (pinfunction "GND_3") (pintype "passive"))
      (node (ref "GRB12") (pin "3") (pinfunction "GND_3") (pintype "passive"))
      (node (ref "GRB13") (pin "3") (pinfunction "GND_3") (pintype "passive"))
      (node (ref "GRB14") (pin "3") (pinfunction "GND_3") (pintype "passive"))
      (node (ref "GRB15") (pin "3") (pinfunction "GND_3") (pintype "passive"))
      (node (ref "GRB16") (pin "3") (pinfunction "GND_3") (pintype "passive"))
      (node (ref "GRB17") (pin "3") (pinfunction "GND_3") (pintype "passive"))
      (node (ref "GRB18") (pin "3") (pinfunction "GND_3") (pintype "passive"))
      (node (ref "GRB19") (pin "3") (pinfunction "GND_3") (pintype "passive"))
      (node (ref "GRB2") (pin "3") (pinfunction "GND_3") (pintype "passive"))
      (node (ref "GRB20") (pin "3") (pinfunction "GND_3") (pintype "passive"))
      (node (ref "GRB21") (pin "3") (pinfunction "GND_3") (pintype "passive"))
      (node (ref "GRB22") (pin "3") (pinfunction "GND_3") (pintype "passive"))
      (node (ref "GRB23") (pin "3") (pinfunction "GND_3") (pintype "passive"))
      (node (ref "GRB24") (pin "3") (pinfunction "GND_3") (pintype "passive"))
      (node (ref "GRB25") (pin "3") (pinfunction "GND_3") (pintype "passive"))
      (node (ref "GRB26") (pin "3") (pinfunction "GND_3") (pintype "passive"))
      (node (ref "GRB27") (pin "3") (pinfunction "GND_3") (pintype "passive"))
      (node (ref "GRB3") (pin "3") (pinfunction "GND_3") (pintype "passive"))
      (node (ref "GRB4") (pin "3") (pinfunction "GND_3") (pintype "passive"))
      (node (ref "GRB5") (pin "3") (pinfunction "GND_3") (pintype "passive"))
      (node (ref "GRB6") (pin "3") (pinfunction "GND_3") (pintype "passive"))
      (node (ref "GRB7") (pin "3") (pinfunction "GND_3") (pintype "passive"))
      (node (ref "GRB8") (pin "3") (pinfunction "GND_3") (pintype "passive"))
      (node (ref "GRB9") (pin "3") (pinfunction "GND_3") (pintype "passive"))
      (node (ref "JP1") (pin "4") (pinfunction "4_4") (pintype "passive"))
      (node (ref "Q3") (pin "2") (pinfunction "e_2") (pintype "passive"))
      (node (ref "Q4") (pin "2") (pinfunction "e_2") (pintype "passive"))
      (node (ref "Q5") (pin "2") (pinfunction "e_2") (pintype "passive"))
      (node (ref "R22") (pin "1") (pinfunction "1_1") (pintype "passive"))
      (node (ref "R23") (pin "1") (pinfunction "1_1") (pintype "passive"))
      (node (ref "R24") (pin "1") (pinfunction "1_1") (pintype "passive"))
      (node (ref "R4") (pin "1") (pinfunction "1_1") (pintype "passive"))
      (node (ref "REC1") (pin "2") (pinfunction "GND_2") (pintype "passive"))
      (node (ref "REC2") (pin "2") (pinfunction "GND_2") (pintype "passive"))
      (node (ref "SWD1") (pin "2") (pinfunction "2_2") (pintype "passive"))
      (node (ref "U1") (pin "23") (pinfunction "VSS_23") (pintype "passive"))
      (node (ref "U1") (pin "44") (pinfunction "BOOT0_44") (pintype "passive"))
      (node (ref "U1") (pin "47") (pinfunction "VSS_47") (pintype "passive"))
      (node (ref "U1") (pin "8") (pinfunction "VSSA_8") (pintype "passive"))
      (node (ref "U2") (pin "2") (pinfunction "GND_2") (pintype "passive"))
      (node (ref "U3") (pin "1") (pinfunction "G_1") (pintype "passive"))
      (node (ref "U4") (pin "4") (pinfunction "GND_4") (pintype "passive"))
      (node (ref "U5") (pin "2") (pinfunction "GND_2") (pintype "passive"))
      (node (ref "U6") (pin "2") (pinfunction "GND_2") (pintype "passive"))
      (node (ref "U7") (pin "2") (pinfunction "GND_2") (pintype "passive"))
      (node (ref "UART") (pin "2") (pinfunction "2_2") (pintype "passive"))
    )
    (net (code "67") (name "Net-(D1-A)") (class "Default")
      (node (ref "D1") (pin "1") (pinfunction "A_1") (pintype "passive"))
      (node (ref "R13") (pin "2") (pinfunction "2_2") (pintype "passive"))
    )
    (net (code "68") (name "Net-(D1-K)") (class "Default")
      (node (ref "D1") (pin "2") (pinfunction "K_2") (pintype "passive"))
      (node (ref "Q4") (pin "3") (pinfunction "c_3") (pintype "passive"))
    )
    (net (code "69") (name "Net-(D2-A)") (class "Default")
      (node (ref "D2") (pin "1") (pinfunction "A_1") (pintype "passive"))
      (node (ref "R14") (pin "2") (pinfunction "2_2") (pintype "passive"))
    )
    (net (code "70") (name "Net-(D2-K)") (class "Default")
      (node (ref "D2") (pin "2") (pinfunction "K_2") (pintype "passive"))
      (node (ref "Q5") (pin "3") (pinfunction "c_3") (pintype "passive"))
    )
    (net (code "71") (name "Net-(Q1-G)") (class "Default")
      (node (ref "Q1") (pin "1") (pinfunction "G_1") (pintype "passive"))
      (node (ref "R5") (pin "1") (pinfunction "1_1") (pintype "passive"))
    )
    (net (code "72") (name "Net-(Q2-G)") (class "Default")
      (node (ref "Q2") (pin "1") (pinfunction "G_1") (pintype "passive"))
      (node (ref "R6") (pin "1") (pinfunction "1_1") (pintype "passive"))
    )
    (net (code "73") (name "Net-(Q3-b)") (class "Default")
      (node (ref "Q3") (pin "1") (pinfunction "b_1") (pintype "passive"))
      (node (ref "R19") (pin "2") (pinfunction "2_2") (pintype "passive"))
      (node (ref "R22") (pin "2") (pinfunction "2_2") (pintype "passive"))
    )
    (net (code "74") (name "Net-(Q3-c)") (class "Default")
      (node (ref "B1") (pin "2") (pinfunction "2_2") (pintype "passive"))
      (node (ref "Q3") (pin "3") (pinfunction "c_3") (pintype "passive"))
    )
    (net (code "75") (name "Net-(Q4-b)") (class "Default")
      (node (ref "Q4") (pin "1") (pinfunction "b_1") (pintype "passive"))
      (node (ref "R20") (pin "2") (pinfunction "2_2") (pintype "passive"))
      (node (ref "R23") (pin "2") (pinfunction "2_2") (pintype "passive"))
    )
    (net (code "76") (name "Net-(Q5-b)") (class "Default")
      (node (ref "Q5") (pin "1") (pinfunction "b_1") (pintype "passive"))
      (node (ref "R21") (pin "2") (pinfunction "2_2") (pintype "passive"))
      (node (ref "R24") (pin "2") (pinfunction "2_2") (pintype "passive"))
    )
    (net (code "77") (name "Net-(R25-Pad1)") (class "Default")
      (node (ref "R25") (pin "1") (pinfunction "1_1") (pintype "passive"))
      (node (ref "T1") (pin "1") (pintype "passive"))
    )
    (net (code "78") (name "Net-(R26-Pad1)") (class "Default")
      (node (ref "R26") (pin "1") (pinfunction "1_1") (pintype "passive"))
      (node (ref "T2") (pin "1") (pintype "passive"))
    )
    (net (code "79") (name "Net-(R27-Pad1)") (class "Default")
      (node (ref "R27") (pin "1") (pinfunction "1_1") (pintype "passive"))
      (node (ref "T3") (pin "1") (pintype "passive"))
    )
    (net (code "80") (name "Net-(REC1-OUT)") (class "Default")
      (node (ref "R11") (pin "1") (pinfunction "1_1") (pintype "passive"))
      (node (ref "R15") (pin "1") (pinfunction "1_1") (pintype "passive"))
      (node (ref "REC1") (pin "1") (pinfunction "OUT_1") (pintype "passive"))
    )
    (net (code "81") (name "Net-(REC1-VCC)") (class "Default")
      (node (ref "R17") (pin "1") (pinfunction "1_1") (pintype "passive"))
      (node (ref "REC1") (pin "3") (pinfunction "VCC_3") (pintype "passive"))
    )
    (net (code "82") (name "Net-(REC2-OUT)") (class "Default")
      (node (ref "R12") (pin "1") (pinfunction "1_1") (pintype "passive"))
      (node (ref "R16") (pin "1") (pinfunction "1_1") (pintype "passive"))
      (node (ref "REC2") (pin "1") (pinfunction "OUT_1") (pintype "passive"))
    )
    (net (code "83") (name "Net-(REC2-VCC)") (class "Default")
      (node (ref "R18") (pin "1") (pinfunction "1_1") (pintype "passive"))
      (node (ref "REC2") (pin "3") (pinfunction "VCC_3") (pintype "passive"))
    )
    (net (code "84") (name "Net-(U2-BS)") (class "Default")
      (node (ref "C4") (pin "1") (pinfunction "1_1") (pintype "passive"))
      (node (ref "U2") (pin "1") (pinfunction "BS_1") (pintype "passive"))
    )
    (net (code "85") (name "Net-(U2-EN)") (class "Default")
      (node (ref "R3") (pin "2") (pinfunction "2_2") (pintype "passive"))
      (node (ref "U2") (pin "4") (pinfunction "EN_4") (pintype "passive"))
    )
    (net (code "86") (name "Net-(U2-FB)") (class "Default")
      (node (ref "R2") (pin "1") (pinfunction "1_1") (pintype "passive"))
      (node (ref "R4") (pin "2") (pinfunction "2_2") (pintype "passive"))
      (node (ref "U2") (pin "3") (pinfunction "FB_3") (pintype "passive"))
    )
    (net (code "87") (name "Net-(U2-SW)") (class "Default")
      (node (ref "C4") (pin "2") (pinfunction "2_2") (pintype "passive"))
      (node (ref "L1") (pin "1") (pinfunction "1_1") (pintype "passive"))
      (node (ref "U2") (pin "6") (pinfunction "SW_6") (pintype "passive"))
    )
    (net (code "88") (name "Net-(U5-KEY)") (class "Default")
      (node (ref "R25") (pin "2") (pinfunction "2_2") (pintype "passive"))
      (node (ref "U5") (pin "3") (pinfunction "KEY_3") (pintype "passive"))
    )
    (net (code "89") (name "Net-(U5-TOG)") (class "Default")
      (node (ref "C45") (pin "1") (pinfunction "1_1") (pintype "passive"))
      (node (ref "U5") (pin "6") (pinfunction "TOG_6") (pintype "passive"))
    )
    (net (code "90") (name "Net-(U6-KEY)") (class "Default")
      (node (ref "R26") (pin "2") (pinfunction "2_2") (pintype "passive"))
      (node (ref "U6") (pin "3") (pinfunction "KEY_3") (pintype "passive"))
    )
    (net (code "91") (name "Net-(U6-TOG)") (class "Default")
      (node (ref "C46") (pin "1") (pinfunction "1_1") (pintype "passive"))
      (node (ref "U6") (pin "6") (pinfunction "TOG_6") (pintype "passive"))
    )
    (net (code "92") (name "Net-(U7-KEY)") (class "Default")
      (node (ref "R27") (pin "2") (pinfunction "2_2") (pintype "passive"))
      (node (ref "U7") (pin "3") (pinfunction "KEY_3") (pintype "passive"))
    )
    (net (code "93") (name "Net-(U7-TOG)") (class "Default")
      (node (ref "C47") (pin "1") (pinfunction "1_1") (pintype "passive"))
      (node (ref "U7") (pin "6") (pinfunction "TOG_6") (pintype "passive"))
    )
    (net (code "94") (name "unconnected-(CON1-Pad3)") (class "Default")
      (node (ref "CON1") (pin "3") (pintype "power_in+no_connect"))
    )
    (net (code "95") (name "unconnected-(GRB3-DOUT-Pad2)") (class "Default")
      (node (ref "GRB3") (pin "2") (pinfunction "DOUT_2") (pintype "passive"))
    )
    (net (code "96") (name "unconnected-(GRB27-DOUT-Pad2)") (class "Default")
      (node (ref "GRB27") (pin "2") (pinfunction "DOUT_2") (pintype "passive"))
    )
    (net (code "97") (name "unconnected-(U1A-PA0-Pad10)") (class "Default")
      (node (ref "U1") (pin "10") (pinfunction "PA0_10") (pintype "passive"))
    )
    (net (code "98") (name "unconnected-(U1A-PA1-Pad11)") (class "Default")
      (node (ref "U1") (pin "11") (pinfunction "PA1_11") (pintype "passive"))
    )
    (net (code "99") (name "unconnected-(U1A-PB0-Pad18)") (class "Default")
      (node (ref "U1") (pin "18") (pinfunction "PB0_18") (pintype "passive"))
    )
    (net (code "100") (name "unconnected-(U1A-PB1-Pad19)") (class "Default")
      (node (ref "U1") (pin "19") (pinfunction "PB1_19") (pintype "passive"))
    )
    (net (code "101") (name "unconnected-(U1A-PB2-Pad20)") (class "Default")
      (node (ref "U1") (pin "20") (pinfunction "PB2_20") (pintype "passive"))
    )
    (net (code "102") (name "unconnected-(U1A-PB4-Pad40)") (class "Default")
      (node (ref "U1") (pin "40") (pinfunction "PB4_40") (pintype "passive"))
    )
    (net (code "103") (name "unconnected-(U1A-PB5-Pad41)") (class "Default")
      (node (ref "U1") (pin "41") (pinfunction "PB5_41") (pintype "passive"))
    )
    (net (code "104") (name "unconnected-(U1A-PB6-Pad42)") (class "Default")
      (node (ref "U1") (pin "42") (pinfunction "PB6_42") (pintype "passive"))
    )
    (net (code "105") (name "unconnected-(U1A-PB7-Pad43)") (class "Default")
      (node (ref "U1") (pin "43") (pinfunction "PB7_43") (pintype "passive"))
    )
    (net (code "106") (name "unconnected-(U1A-PB10-Pad21)") (class "Default")
      (node (ref "U1") (pin "21") (pinfunction "PB10_21") (pintype "passive"))
    )
    (net (code "107") (name "unconnected-(U1A-PB11-Pad22)") (class "Default")
      (node (ref "U1") (pin "22") (pinfunction "PB11_22") (pintype "passive"))
    )
    (net (code "108") (name "unconnected-(U1A-PB13-Pad26)") (class "Default")
      (node (ref "U1") (pin "26") (pinfunction "PB13_26") (pintype "passive"))
    )
    (net (code "109") (name "unconnected-(U1A-PB15-Pad28)") (class "Default")
      (node (ref "U1") (pin "28") (pinfunction "PB15_28") (pintype "passive"))
    )
    (net (code "110") (name "unconnected-(U1A-PC13-Pad2)") (class "Default")
      (node (ref "U1") (pin "2") (pinfunction "PC13_2") (pintype "passive"))
    )
    (net (code "111") (name "unconnected-(U1A-PC14-OSC32_IN(PC14)-Pad3)") (class "Default")
      (node (ref "U1") (pin "3") (pinfunction "PC14-OSC32_IN(PC14)_3") (pintype "passive"))
    )
    (net (code "112") (name "unconnected-(U1A-PC15-OSC32_OUT(PC15)-Pad4)") (class "Default")
      (node (ref "U1") (pin "4") (pinfunction "PC15-OSC32_OUT(PC15)_4") (pintype "passive"))
    )
    (net (code "113") (name "unconnected-(U1A-PF6-Pad35)") (class "Default")
      (node (ref "U1") (pin "35") (pinfunction "PF6_35") (pintype "passive"))
    )
    (net (code "114") (name "unconnected-(U1A-PF7-Pad36)") (class "Default")
      (node (ref "U1") (pin "36") (pinfunction "PF7_36") (pintype "passive"))
    )
    (net (code "115") (name "unconnected-(U5-AHLB-Pad4)") (class "Default")
      (node (ref "U5") (pin "4") (pinfunction "AHLB_4") (pintype "passive"))
    )
    (net (code "116") (name "unconnected-(U6-AHLB-Pad4)") (class "Default")
      (node (ref "U6") (pin "4") (pinfunction "AHLB_4") (pintype "passive"))
    )
    (net (code "117") (name "unconnected-(U7-AHLB-Pad4)") (class "Default")
      (node (ref "U7") (pin "4") (pinfunction "AHLB_4") (pintype "passive"))
    )
  )
)
